# DriveMoteur.net
KiCad netlist of a schematic drawn in Altium Designer
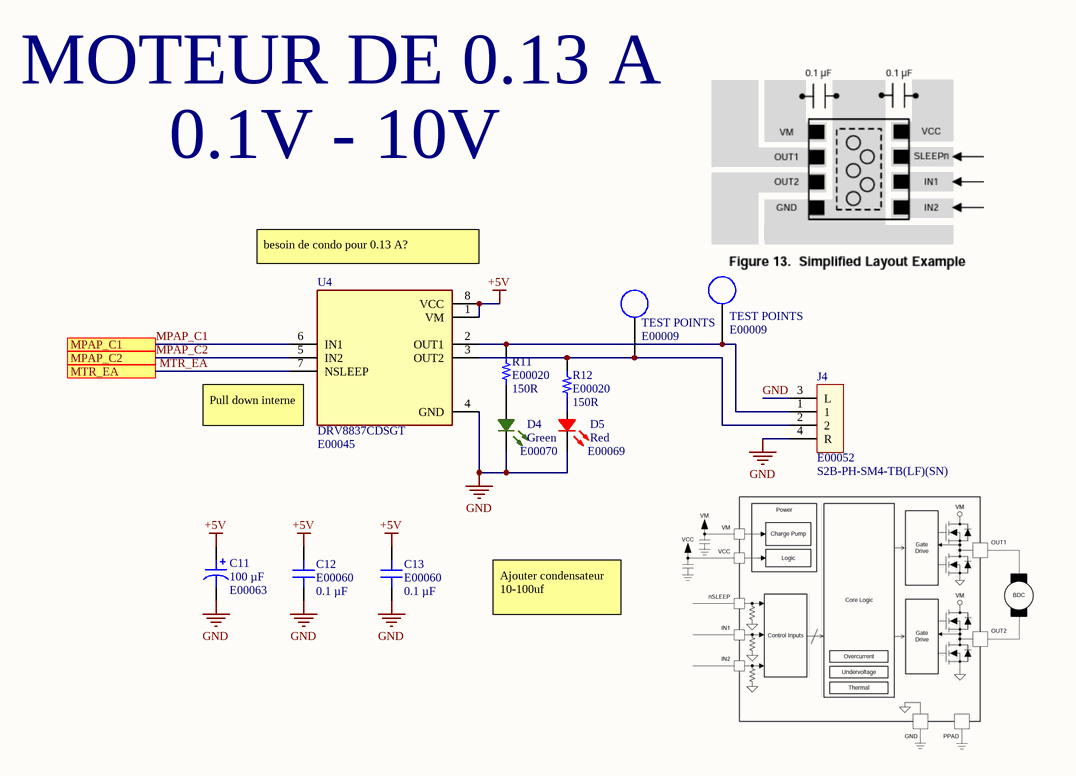
[diagram p0: DriveMoteur.SchDoc]

(export (version "E")
  (design (tool "Eeschema 10.0.6"))
  (components
    (comp (ref "C11")
      (value "100 µF")
      (footprint "CAP ALSMD ELEC 8.3MM H10.5MM")
      (description "CAP ALUM 100UF 20% 50V SMD")
      (fields
        (field (name "MANUFACTURER") "Nichicon")
        (field (name "TOLERANCE") "±20%")
        (field (name "ADAM INVENTORY NUMBER 1") "E00063")
      )
      (libsource (lib "ADAM LIBRARY") (part "CAP ALUM 100UF 20% 50V SMD"))
    )
    (comp (ref "C12")
      (value "0.1 µF")
      (footprint "CAP 0603")
      (description "CAP CER 0.1UF 50V X7R 0603")
      (fields
        (field (name "MANUFACTURER") "KEMET")
        (field (name "TOLERANCE") "±10%")
        (field (name "ADAM INVENTORY NUMBER 1") "E00060")
      )
      (libsource (lib "ADAM LIBRARY") (part "CAP CER 0.1UF 50V X7R 0603"))
    )
    (comp (ref "C13")
      (value "0.1 µF")
      (footprint "CAP 0603")
      (description "CAP CER 0.1UF 50V X7R 0603")
      (fields
        (field (name "MANUFACTURER") "KEMET")
        (field (name "TOLERANCE") "±10%")
        (field (name "ADAM INVENTORY NUMBER 1") "E00060")
      )
      (libsource (lib "ADAM LIBRARY") (part "CAP CER 0.1UF 50V X7R 0603"))
    )
    (comp (ref "D4")
      (value "Green")
      (footprint "Green LED 0603")
      (description "LED GREEN 0603 SMD")
      (fields (field (name "MANUFACTURER") "Dialight") (field (name "ADAM INVENTORY NUMBER 1") "E00070"))
      (libsource (lib "ADAM LIBRARY") (part "0603 GREEN LED"))
    )
    (comp (ref "D5")
      (value "Red")
      (footprint "Red Led 0603")
      (description "0603 RED LED")
      (fields
        (field (name "MANUFACTURER") "American Bright Optoelectronics Corporation")
        (field (name "ADAM INVENTORY NUMBER 1") "E00069")
      )
      (libsource (lib "ADAM LIBRARY") (part "0603 RED LED"))
    )
    (comp (ref "J4")
      (value "CONN JST 2P SM 90DEG")
      (footprint "S2B-PH-SM4-TB_LF__SN")
      (description "CONN SM JST 2P")
      (fields
        (field (name "ADAM INVENTORY NUMBER 1") "E00052")
        (field (name "SUPPLIER PART NUMBER 1") "S2B-PH-SM4-TB(LF)(SN)")
        (field (name "COPYRIGHT") "Copyright (C) 2023 Ultra Librarian. All rights reserved.")
      )
      (libsource (lib "ADAM LIBRARY") (part "CONN JST 2P SM 90DEG"))
    )
    (comp (ref "M+")
      (value "TEST POINTS")
      (footprint "TEST POINTS")
      (description "RCWCTE TEST POINTS")
      (fields (field (name "ADAM INVENTORY NUMBER 1") "E00009"))
      (libsource (lib "ADAM LIBRARY") (part "TEST POINTS"))
    )
    (comp (ref "M-")
      (value "TEST POINTS")
      (footprint "TEST POINTS")
      (description "RCWCTE TEST POINTS")
      (fields (field (name "ADAM INVENTORY NUMBER 1") "E00009"))
      (libsource (lib "ADAM LIBRARY") (part "TEST POINTS"))
    )
    (comp (ref "R11")
      (value "150R")
      (footprint "RES 0603")
      (description "RES SMD 150 OHM 0.1% 1/8W 0603")
      (fields
        (field (name "MANUFACTURER") "Vishay Beyschlag")
        (field (name "TOLERANCE") "±0.1%")
        (field (name "ADAM INVENTORY NUMBER 1") "E00020")
      )
      (libsource (lib "ADAM LIBRARY") (part "RES SMD 150 OHM"))
    )
    (comp (ref "R12")
      (value "150R")
      (footprint "RES 0603")
      (description "RES SMD 150 OHM 0.1% 1/8W 0603")
      (fields
        (field (name "MANUFACTURER") "Vishay Beyschlag")
        (field (name "TOLERANCE") "±0.1%")
        (field (name "ADAM INVENTORY NUMBER 1") "E00020")
      )
      (libsource (lib "ADAM LIBRARY") (part "RES SMD 150 OHM"))
    )
    (comp (ref "U4")
      (value "DRV8837CDSGT")
      (footprint "DRV8837CDSGT")
      (description "Motor Driver NMOS PWM 8-WSON (2x2)")
      (fields (field (name "ADAM INVENTORY NUMBER 1") "E00045"))
      (libsource (lib "ADAM LIBRARY") (part "DRV8837CDSGT"))
    )
  )
  (nets
    (net (code "1") (name "+5V") (class "Default")
      (node (ref "C11") (pin "1") (pinfunction "1_1") (pintype "passive"))
      (node (ref "C12") (pin "2") (pinfunction "2_2") (pintype "passive"))
      (node (ref "C13") (pin "2") (pinfunction "2_2") (pintype "passive"))
      (node (ref "U4") (pin "1") (pinfunction "VM_1") (pintype "passive"))
      (node (ref "U4") (pin "8") (pinfunction "VCC_8") (pintype "passive"))
    )
    (net (code "2") (name "/MPAP_C1") (class "Default")
      (node (ref "U4") (pin "6") (pinfunction "IN1_6") (pintype "passive"))
    )
    (net (code "3") (name "/MPAP_C2") (class "Default")
      (node (ref "U4") (pin "5") (pinfunction "IN2_5") (pintype "passive"))
    )
    (net (code "4") (name "/MTR_EA") (class "Default")
      (node (ref "U4") (pin "7") (pinfunction "NSLEEP_7") (pintype "passive"))
    )
    (net (code "5") (name "GND") (class "Default")
      (node (ref "C11") (pin "2") (pinfunction "2_2") (pintype "passive"))
      (node (ref "C12") (pin "1") (pinfunction "1_1") (pintype "passive"))
      (node (ref "C13") (pin "1") (pinfunction "1_1") (pintype "passive"))
      (node (ref "D4") (pin "2") (pinfunction "2_2") (pintype "passive"))
      (node (ref "D5") (pin "2") (pinfunction "2_2") (pintype "passive"))
      (node (ref "J4") (pin "3") (pinfunction "L_3") (pintype "passive"))
      (node (ref "J4") (pin "4") (pinfunction "R_4") (pintype "passive"))
      (node (ref "U4") (pin "4") (pinfunction "GND_4") (pintype "passive"))
    )
    (net (code "6") (name "Net-(D4-Pad1)") (class "Default")
      (node (ref "D4") (pin "1") (pinfunction "1_1") (pintype "passive"))
      (node (ref "R11") (pin "1") (pinfunction "1_1") (pintype "passive"))
    )
    (net (code "7") (name "Net-(D5-Pad1)") (class "Default")
      (node (ref "D5") (pin "1") (pinfunction "1_1") (pintype "passive"))
      (node (ref "R12") (pin "1") (pinfunction "1_1") (pintype "passive"))
    )
    (net (code "8") (name "Net-(U4-OUT1)") (class "Default")
      (node (ref "J4") (pin "1") (pinfunction "1_1") (pintype "passive"))
      (node (ref "M+") (pin "1") (pinfunction "1_1") (pintype "passive"))
      (node (ref "R11") (pin "2") (pinfunction "2_2") (pintype "passive"))
      (node (ref "U4") (pin "2") (pinfunction "OUT1_2") (pintype "passive"))
    )
    (net (code "9") (name "Net-(U4-OUT2)") (class "Default")
      (node (ref "J4") (pin "2") (pinfunction "2_2") (pintype "passive"))
      (node (ref "M-") (pin "1") (pinfunction "1_1") (pintype "passive"))
      (node (ref "R12") (pin "2") (pinfunction "2_2") (pintype "passive"))
      (node (ref "U4") (pin "3") (pinfunction "OUT2_3") (pintype "passive"))
    )
  )
)
